# USB.net
KiCad netlist of a schematic drawn in Altium Designer
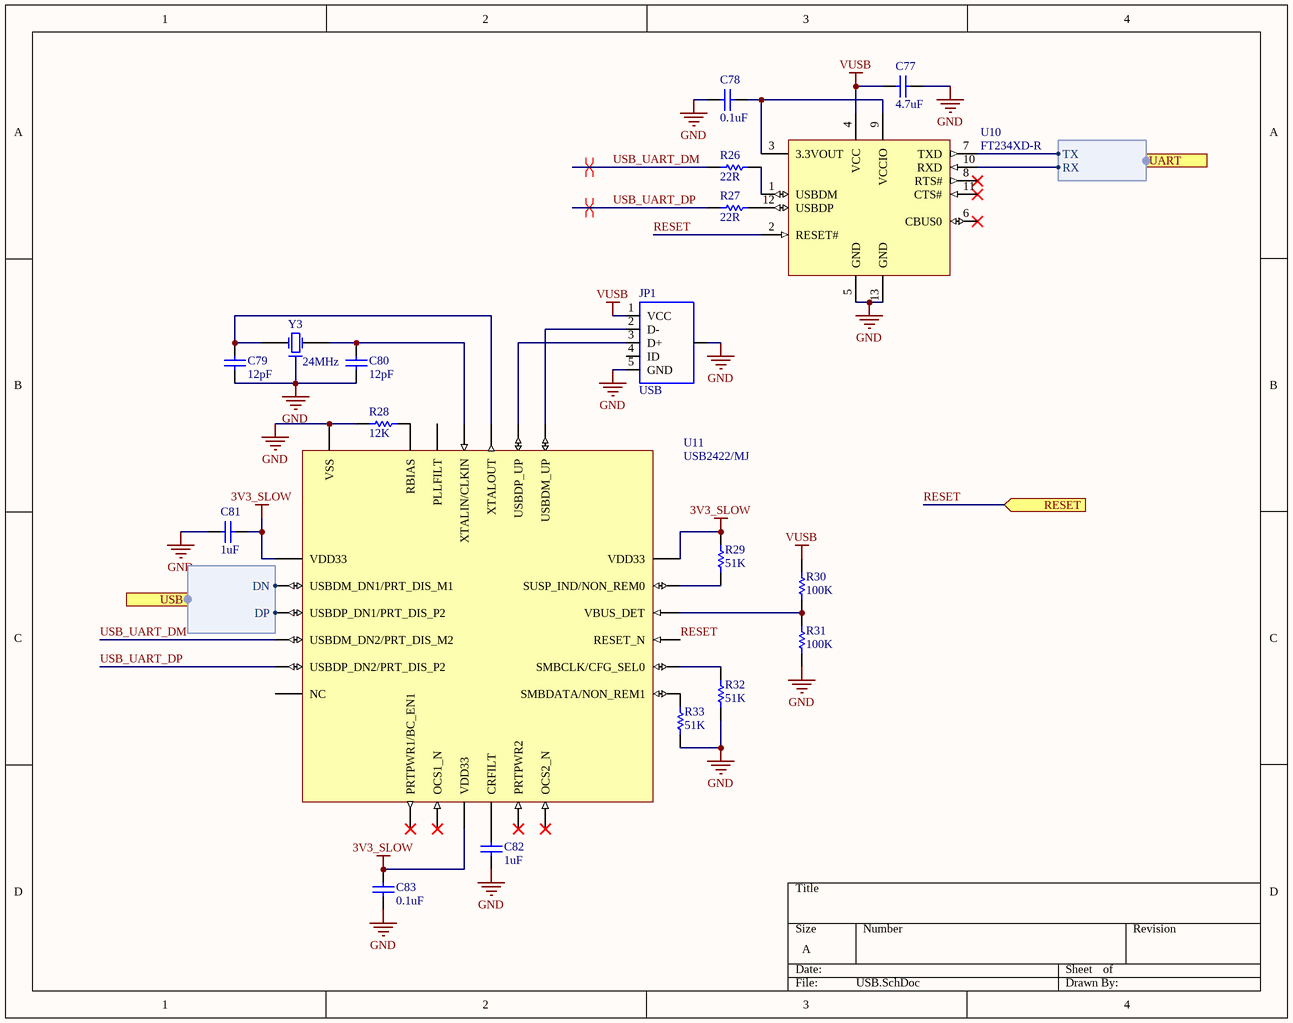
[diagram p0: USB.SchDoc]

(export (version "E")
  (design (tool "Eeschema 10.0.6"))
  (components
    (comp (ref "C77")
      (value "4.7uF")
      (footprint "C0402[1005X55]")
      (description "4.7uF 6.3V 20% 0402 (1005 Metric)")
      (fields (field (name "PARTNUMBER") "GRM155R60J475ME47D") (field (name "MANUFACTURER") "Murata"))
      (libsource (lib "Capacitors") (part "CAP_4.7uF_6.3V_0402_20%"))
    )
    (comp (ref "C78")
      (value "0.1uF")
      (footprint "C0402[1005X55]")
      (description "0.1uF 6.3V 10% 0402 (1005 Metric)")
      (fields (field (name "PARTNUMBER") "GRM155R70J104KA01D") (field (name "MANUFACTURER") "Murata"))
      (libsource (lib "Capacitors") (part "CAP_0.1uF_6.3V_0402_10%"))
    )
    (comp (ref "C79")
      (value "12pF")
      (footprint "C0402[1005X55]")
      (description "12pF 50V 5% 0402 (1005 Metric)")
      (fields (field (name "PARTNUMBER") "GRM1555C1H120JA01D") (field (name "MANUFACTURER") "Murata"))
      (libsource (lib "Capacitors") (part "CAP_12pF_50V_0402_5%"))
    )
    (comp (ref "C80")
      (value "12pF")
      (footprint "C0402[1005X55]")
      (description "12pF 50V 5% 0402 (1005 Metric)")
      (fields (field (name "PARTNUMBER") "GRM1555C1H120JA01D") (field (name "MANUFACTURER") "Murata"))
      (libsource (lib "Capacitors") (part "CAP_12pF_50V_0402_5%"))
    )
    (comp (ref "C81")
      (value "1uF")
      (footprint "C0402[1005X55]")
      (description "1uF 6.3V 10% 0402 (1005 Metric)")
      (fields (field (name "PARTNUMBER") "GRM155R70J105KA12D") (field (name "MANUFACTURER") "Murata"))
      (libsource (lib "Capacitors") (part "CAP_1uF_6.3V_0402_10%"))
    )
    (comp (ref "C82")
      (value "1uF")
      (footprint "C0402[1005X55]")
      (description "1uF 6.3V 10% 0402 (1005 Metric)")
      (fields (field (name "PARTNUMBER") "GRM155R70J105KA12D") (field (name "MANUFACTURER") "Murata"))
      (libsource (lib "Capacitors") (part "CAP_1uF_6.3V_0402_10%"))
    )
    (comp (ref "C83")
      (value "0.1uF")
      (footprint "C0402[1005X55]")
      (description "0.1uF 6.3V 10% 0402 (1005 Metric)")
      (fields (field (name "PARTNUMBER") "GRM155R70J104KA01D") (field (name "MANUFACTURER") "Murata"))
      (libsource (lib "Capacitors") (part "CAP_0.1uF_6.3V_0402_10%"))
    )
    (comp (ref "JP1")
      (value "USB")
      (footprint "USB-MICROB")
      (fields (field (name "PARTNUMBER") "10118192-0001LF") (field (name "MANUFACTURER") "Amphenol FCI"))
      (libsource (lib "Connectors") (part "USB_MICROB_SMT"))
    )
    (comp (ref "R26")
      (value "22R")
      (footprint "R0402[1005]")
      (description "22R 0.063W 1% 0402 (1005 Metric)")
      (fields (field (name "MANUFACTURER") "KOA Speer") (field (name "PARTNUMBER") "RK73H1ETTP22R0F"))
      (libsource (lib "Resistors") (part "RES_22R_0402_1%"))
    )
    (comp (ref "R27")
      (value "22R")
      (footprint "R0402[1005]")
      (description "22R 0.063W 1% 0402 (1005 Metric)")
      (fields (field (name "MANUFACTURER") "KOA Speer") (field (name "PARTNUMBER") "RK73H1ETTP22R0F"))
      (libsource (lib "Resistors") (part "RES_22R_0402_1%"))
    )
    (comp (ref "R28")
      (value "12K")
      (footprint "R0402[1005]")
      (description "12K 0.063W 1% 0402 (1005 Metric)")
      (fields (field (name "MANUFACTURER") "KOA Speer") (field (name "PARTNUMBER") "RK73H1ETTP1202F"))
      (libsource (lib "Resistors") (part "RES_12K_0402_1%"))
    )
    (comp (ref "R29")
      (value "51K")
      (footprint "R0402[1005]")
      (description "51K 0.063W 1% 0402 (1005 Metric)")
      (fields (field (name "MANUFACTURER") "KOA Speer") (field (name "PARTNUMBER") "RK73H1ETTP5102F"))
      (libsource (lib "Resistors") (part "RES_51K_0402_1%"))
    )
    (comp (ref "R30")
      (value "100K")
      (footprint "R0402[1005]")
      (description "100K 0.063W 1% 0402 (1005 Metric)")
      (fields (field (name "MANUFACTURER") "KOA Speer") (field (name "PARTNUMBER") "RK73H1ETTP1003F"))
      (libsource (lib "Resistors") (part "RES_100K_0402_1%"))
    )
    (comp (ref "R31")
      (value "100K")
      (footprint "R0402[1005]")
      (description "100K 0.063W 1% 0402 (1005 Metric)")
      (fields (field (name "MANUFACTURER") "KOA Speer") (field (name "PARTNUMBER") "RK73H1ETTP1003F"))
      (libsource (lib "Resistors") (part "RES_100K_0402_1%"))
    )
    (comp (ref "R32")
      (value "51K")
      (footprint "R0402[1005]")
      (description "51K 0.063W 1% 0402 (1005 Metric)")
      (fields (field (name "MANUFACTURER") "KOA Speer") (field (name "PARTNUMBER") "RK73H1ETTP5102F"))
      (libsource (lib "Resistors") (part "RES_51K_0402_1%"))
    )
    (comp (ref "R33")
      (value "51K")
      (footprint "R0402[1005]")
      (description "51K 0.063W 1% 0402 (1005 Metric)")
      (fields (field (name "MANUFACTURER") "KOA Speer") (field (name "PARTNUMBER") "RK73H1ETTP5102F"))
      (libsource (lib "Resistors") (part "RES_51K_0402_1%"))
    )
    (comp (ref "U10")
      (value "FT234XD-R")
      (footprint "DFN-12")
      (description "USB Interface IC USB to Serial UART Interface")
      (fields (field (name "MANUFACTURER") "FTDI"))
      (libsource (lib "ICs") (part "FT234XD-R"))
    )
    (comp (ref "U11")
      (value "USB2422/MJ")
      (footprint "QFN-24 (4x4MM)")
      (description "USB Hub IC 2-Port")
      (fields (field (name "MANUFACTURER") "Microchip"))
      (libsource (lib "ICs-USBInterface") (part "USB2422/MJ"))
    )
    (comp (ref "Y3")
      (value "24MHz")
      (footprint "CRYSTAL_2.0x1.6")
      (fields (field (name "PARTNUMBER") "FA-128 24.0000MF10Z-W3") (field (name "MANUFACTURER") "EPSON"))
      (libsource (lib "Components") (part "FA-128 24.0000MF10Z-W3"))
    )
  )
  (nets
    (net (code "3") (name "/DN") (class "Default")
      (node (ref "U11") (pin "2") (pinfunction "USBDM_DN1/PRT_DIS_M1_2") (pintype "bidirectional"))
    )
    (net (code "4") (name "/DP") (class "Default")
      (node (ref "U11") (pin "3") (pinfunction "USBDP_DN1/PRT_DIS_P2_3") (pintype "bidirectional"))
    )
    (net (code "5") (name "/RESET") (class "Default")
      (node (ref "U10") (pin "2") (pinfunction "RESET#_2") (pintype "input"))
      (node (ref "U11") (pin "15") (pinfunction "RESET_N_15") (pintype "input"))
    )
    (net (code "6") (name "/RX") (class "Default")
      (node (ref "U10") (pin "10") (pinfunction "RXD_10") (pintype "input"))
    )
    (net (code "7") (name "/TX") (class "Default")
      (node (ref "U10") (pin "7") (pinfunction "TXD_7") (pintype "output"))
    )
    (net (code "8") (name "/USB_UART_DM") (class "Default")
      (node (ref "R26") (pin "1") (pinfunction "1_1") (pintype "passive"))
      (node (ref "U11") (pin "4") (pinfunction "USBDM_DN2/PRT_DIS_M2_4") (pintype "bidirectional"))
    )
    (net (code "9") (name "/USB_UART_DP") (class "Default")
      (node (ref "R27") (pin "1") (pinfunction "1_1") (pintype "passive"))
      (node (ref "U11") (pin "5") (pinfunction "USBDP_DN2/PRT_DIS_P2_5") (pintype "bidirectional"))
    )
    (net (code "12") (name "3V3_SLOW") (class "Default")
      (node (ref "C81") (pin "2") (pinfunction "2_2") (pintype "passive"))
      (node (ref "C83") (pin "2") (pinfunction "2_2") (pintype "passive"))
      (node (ref "R29") (pin "2") (pinfunction "2_2") (pintype "passive"))
      (node (ref "U11") (pin "1") (pinfunction "VDD33_1") (pintype "power_in"))
      (node (ref "U11") (pin "18") (pinfunction "VDD33_18") (pintype "power_in"))
      (node (ref "U11") (pin "9") (pinfunction "VDD33_9") (pintype "power_in"))
    )
    (net (code "13") (name "GND") (class "Default")
      (node (ref "C77") (pin "2") (pinfunction "2_2") (pintype "passive"))
      (node (ref "C78") (pin "2") (pinfunction "2_2") (pintype "passive"))
      (node (ref "C79") (pin "1") (pinfunction "1_1") (pintype "passive"))
      (node (ref "C80") (pin "1") (pinfunction "1_1") (pintype "passive"))
      (node (ref "C81") (pin "1") (pinfunction "1_1") (pintype "passive"))
      (node (ref "C82") (pin "1") (pinfunction "1_1") (pintype "passive"))
      (node (ref "C83") (pin "1") (pinfunction "1_1") (pintype "passive"))
      (node (ref "JP1") (pin "5") (pinfunction "GND_5") (pintype "passive"))
      (node (ref "JP1") (pin "6") (pinfunction "SHIELD_6") (pintype "passive"))
      (node (ref "R28") (pin "1") (pinfunction "1_1") (pintype "passive"))
      (node (ref "R31") (pin "1") (pinfunction "1_1") (pintype "passive"))
      (node (ref "R32") (pin "1") (pinfunction "1_1") (pintype "passive"))
      (node (ref "R33") (pin "1") (pinfunction "1_1") (pintype "passive"))
      (node (ref "U10") (pin "13") (pinfunction "GND_13") (pintype "power_in"))
      (node (ref "U10") (pin "5") (pinfunction "GND_5") (pintype "power_in"))
      (node (ref "U11") (pin "25") (pinfunction "VSS_25") (pintype "power_in"))
      (node (ref "Y3") (pin "2") (pinfunction "2_2") (pintype "passive"))
    )
    (net (code "14") (name "Net-(JP1-D+)") (class "Default")
      (node (ref "JP1") (pin "3") (pinfunction "D+_3") (pintype "passive"))
      (node (ref "U11") (pin "20") (pinfunction "USBDP_UP_20") (pintype "bidirectional"))
    )
    (net (code "15") (name "Net-(JP1-D-)") (class "Default")
      (node (ref "JP1") (pin "2") (pinfunction "D-_2") (pintype "passive"))
      (node (ref "U11") (pin "19") (pinfunction "USBDM_UP_19") (pintype "bidirectional"))
    )
    (net (code "16") (name "Net-(U10-3.3VOUT)") (class "Default")
      (node (ref "C78") (pin "1") (pinfunction "1_1") (pintype "passive"))
      (node (ref "U10") (pin "3") (pinfunction "3.3VOUT_3") (pintype "power_in"))
      (node (ref "U10") (pin "9") (pinfunction "VCCIO_9") (pintype "power_in"))
    )
    (net (code "17") (name "Net-(U10-USBDM)") (class "Default")
      (node (ref "R26") (pin "2") (pinfunction "2_2") (pintype "passive"))
      (node (ref "U10") (pin "1") (pinfunction "USBDM_1") (pintype "bidirectional"))
    )
    (net (code "18") (name "Net-(U10-USBDP)") (class "Default")
      (node (ref "R27") (pin "2") (pinfunction "2_2") (pintype "passive"))
      (node (ref "U10") (pin "12") (pinfunction "USBDP_12") (pintype "bidirectional"))
    )
    (net (code "19") (name "Net-(U11-CRFILT)") (class "Default")
      (node (ref "C82") (pin "2") (pinfunction "2_2") (pintype "passive"))
      (node (ref "U11") (pin "10") (pinfunction "CRFILT_10") (pintype "passive"))
    )
    (net (code "20") (name "Net-(U11-RBIAS)") (class "Default")
      (node (ref "R28") (pin "2") (pinfunction "2_2") (pintype "passive"))
      (node (ref "U11") (pin "24") (pinfunction "RBIAS_24") (pintype "passive"))
    )
    (net (code "21") (name "Net-(U11-SMBCLK{slash}CFG_SEL0)") (class "Default")
      (node (ref "R32") (pin "2") (pinfunction "2_2") (pintype "passive"))
      (node (ref "U11") (pin "14") (pinfunction "SMBCLK/CFG_SEL0_14") (pintype "bidirectional"))
    )
    (net (code "22") (name "Net-(U11-SMBDATA{slash}NON_REM1)") (class "Default")
      (node (ref "R33") (pin "2") (pinfunction "2_2") (pintype "passive"))
      (node (ref "U11") (pin "13") (pinfunction "SMBDATA/NON_REM1_13") (pintype "bidirectional"))
    )
    (net (code "23") (name "Net-(U11-SUSP_IND{slash}NON_REM0)") (class "Default")
      (node (ref "R29") (pin "1") (pinfunction "1_1") (pintype "passive"))
      (node (ref "U11") (pin "17") (pinfunction "SUSP_IND/NON_REM0_17") (pintype "bidirectional"))
    )
    (net (code "24") (name "Net-(U11-VBUS_DET)") (class "Default")
      (node (ref "R30") (pin "1") (pinfunction "1_1") (pintype "passive"))
      (node (ref "R31") (pin "2") (pinfunction "2_2") (pintype "passive"))
      (node (ref "U11") (pin "16") (pinfunction "VBUS_DET_16") (pintype "input"))
    )
    (net (code "25") (name "Net-(U11-XTALIN{slash}CLKIN)") (class "Default")
      (node (ref "C80") (pin "2") (pinfunction "2_2") (pintype "passive"))
      (node (ref "U11") (pin "22") (pinfunction "XTALIN/CLKIN_22") (pintype "input"))
      (node (ref "Y3") (pin "3") (pinfunction "X2_3") (pintype "passive"))
    )
    (net (code "26") (name "Net-(U11-XTALOUT)") (class "Default")
      (node (ref "C79") (pin "2") (pinfunction "2_2") (pintype "passive"))
      (node (ref "U11") (pin "21") (pinfunction "XTALOUT_21") (pintype "output"))
      (node (ref "Y3") (pin "1") (pinfunction "X1_1") (pintype "passive"))
    )
    (net (code "27") (name "VUSB") (class "Default")
      (node (ref "C77") (pin "1") (pinfunction "1_1") (pintype "passive"))
      (node (ref "JP1") (pin "1") (pinfunction "VCC_1") (pintype "passive"))
      (node (ref "R30") (pin "2") (pinfunction "2_2") (pintype "passive"))
      (node (ref "U10") (pin "4") (pinfunction "VCC_4") (pintype "power_in"))
    )
    (net (code "28") (name "unconnected-(JP1-ID-Pad4)") (class "Default")
      (node (ref "JP1") (pin "4") (pinfunction "ID_4") (pintype "passive"))
    )
    (net (code "29") (name "unconnected-(U10-CBUS0-Pad6)") (class "Default")
      (node (ref "U10") (pin "6") (pinfunction "CBUS0_6") (pintype "bidirectional+no_connect"))
    )
    (net (code "30") (name "unconnected-(U10-CTS#-Pad11)") (class "Default")
      (node (ref "U10") (pin "11") (pinfunction "CTS#_11") (pintype "input+no_connect"))
    )
    (net (code "31") (name "unconnected-(U10-RTS#-Pad8)") (class "Default")
      (node (ref "U10") (pin "8") (pinfunction "RTS#_8") (pintype "output+no_connect"))
    )
    (net (code "32") (name "unconnected-(U11-NC-Pad6)") (class "Default")
      (node (ref "U11") (pin "6") (pinfunction "NC_6") (pintype "passive"))
    )
    (net (code "33") (name "unconnected-(U11-OCS1_N-Pad8)") (class "Default")
      (node (ref "U11") (pin "8") (pinfunction "OCS1_N_8") (pintype "input+no_connect"))
    )
    (net (code "34") (name "unconnected-(U11-OCS2_N-Pad12)") (class "Default")
      (node (ref "U11") (pin "12") (pinfunction "OCS2_N_12") (pintype "input+no_connect"))
    )
    (net (code "35") (name "unconnected-(U11-PLLFILT-Pad23)") (class "Default")
      (node (ref "U11") (pin "23") (pinfunction "PLLFILT_23") (pintype "passive"))
    )
    (net (code "36") (name "unconnected-(U11-PRTPWR1{slash}BC_EN1-Pad7)") (class "Default")
      (node (ref "U11") (pin "7") (pinfunction "PRTPWR1/BC_EN1_7") (pintype "output+no_connect"))
    )
    (net (code "37") (name "unconnected-(U11-PRTPWR2-Pad11)") (class "Default")
      (node (ref "U11") (pin "11") (pinfunction "PRTPWR2_11") (pintype "input+no_connect"))
    )
  )
)
